# peripheral.net
KiCad netlist of a schematic drawn in Altium Designer
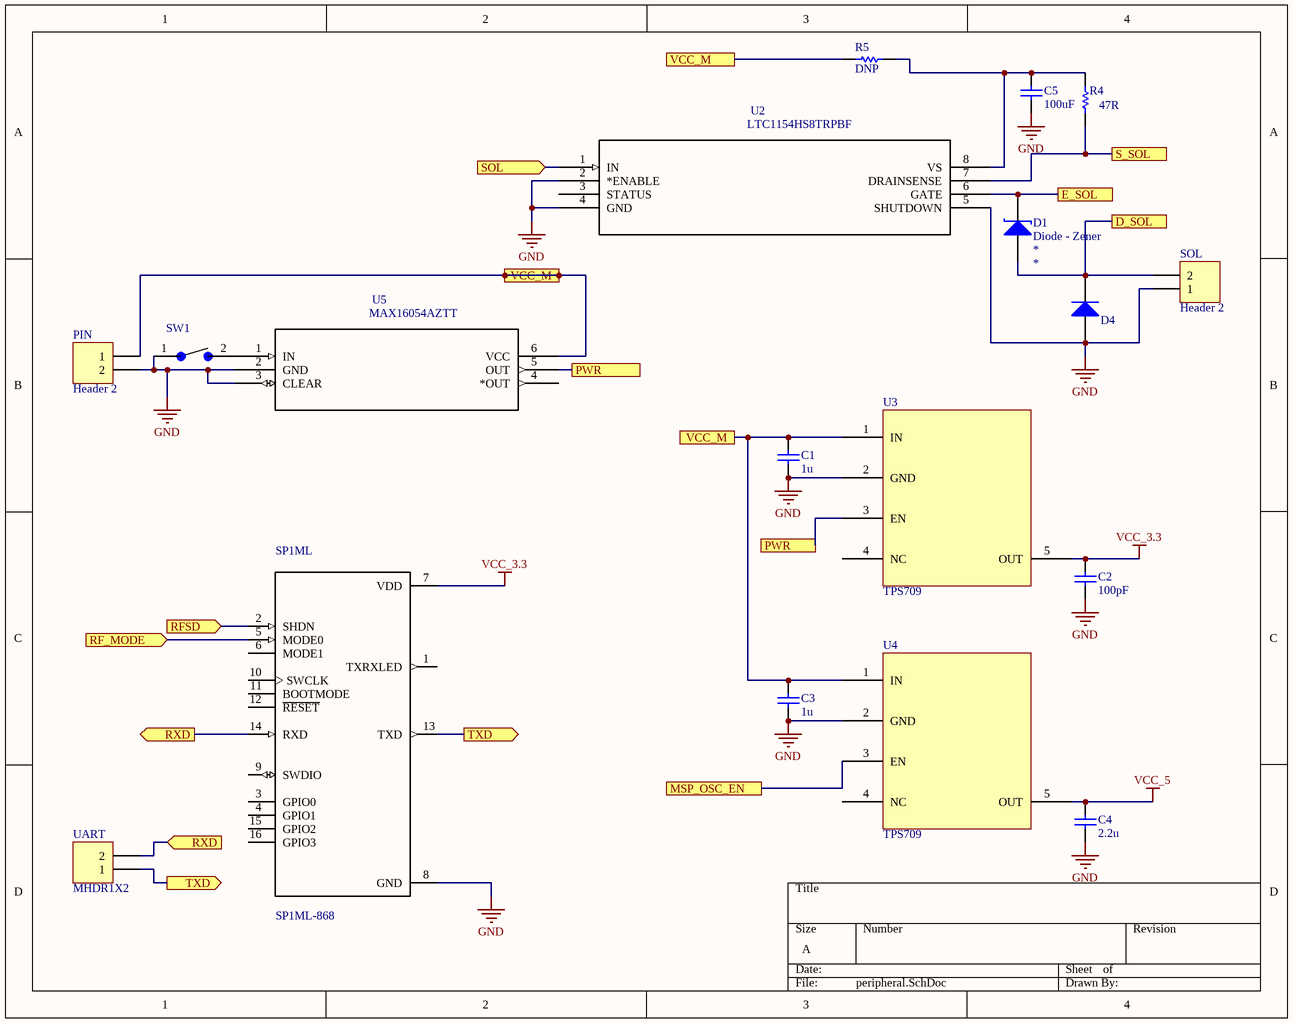
[diagram p0: peripheral.SchDoc]

(export (version "E")
  (design (tool "Eeschema 10.0.6"))
  (components
    (comp (ref "C1")
      (value "1u")
      (footprint "0402-W")
      (description "Ceramic Capacitor (Surface Mount)")
      (fields (field (name "MANUFACTURER") "Generic Ceramic Chip Cap (TBD)") (field (name "Comment") "Cap"))
      (libsource (lib "wisp") (part "Cap"))
    )
    (comp (ref "C2")
      (value "100pF")
      (footprint "0402-W")
      (description "Ceramic Capacitor (Surface Mount)")
      (fields (field (name "MANUFACTURER") "Generic Ceramic Chip Cap (TBD)") (field (name "Comment") "Cap"))
      (libsource (lib "wisp") (part "Cap"))
    )
    (comp (ref "C3")
      (value "1u")
      (footprint "0402-W")
      (description "Ceramic Capacitor (Surface Mount)")
      (fields (field (name "MANUFACTURER") "Generic Ceramic Chip Cap (TBD)") (field (name "Comment") "Cap"))
      (libsource (lib "wisp") (part "Cap"))
    )
    (comp (ref "C4")
      (value "2.2u")
      (footprint "0402-W")
      (description "Ceramic Capacitor (Surface Mount)")
      (fields (field (name "MANUFACTURER") "Generic Ceramic Chip Cap (TBD)") (field (name "Comment") "Cap"))
      (libsource (lib "wisp") (part "Cap"))
    )
    (comp (ref "C5")
      (value "100uF")
      (footprint "0402-W")
      (description "Ceramic Capacitor (Surface Mount)")
      (fields (field (name "MANUFACTURER") "Generic Ceramic Chip Cap (TBD)") (field (name "Comment") "Cap"))
      (libsource (lib "wisp") (part "Cap"))
    )
    (comp (ref "D1")
      (value "Diode - Zener")
      (footprint "SOD-523")
      (fields (field (name "ALTIUM_VALUE") "*") (field (name "RATING") "*"))
      (libsource (lib "wisp") (part "Diode - Zener"))
    )
    (comp (ref "D4")
      (value "Diode")
      (footprint "DIODE - SOD123")
      (description "General Purpose Diode")
      (libsource (lib "wisp") (part "Diode"))
    )
    (comp (ref "PIN")
      (value "Header 2")
      (footprint "HDR1X2")
      (description "Header, 2-Pin")
      (fields (field (name "PUBLISHER") "Altium Limited"))
      (libsource (lib "") (part "Header 2_1"))
    )
    (comp (ref "R4")
      (value "47R")
      (footprint "0402")
      (description "Chip Resistor (Surface Mount)")
      (fields (field (name "MANUFACTURER") "Generic Chip Res (TBD)") (field (name "Comment") "R_Pullup_1"))
      (libsource (lib "WISP_AD10") (part "Res"))
    )
    (comp (ref "R5")
      (value "DNP")
      (footprint "0402")
      (description "Chip Resistor (Surface Mount)")
      (fields (field (name "MANUFACTURER") "Generic Chip Res (TBD)") (field (name "Comment") "R_Pullup_1"))
      (libsource (lib "WISP_AD10") (part "Res"))
    )
    (comp (ref "SOL")
      (value "Header 2")
      (footprint "HDR1X2")
      (description "Header, 2-Pin")
      (fields (field (name "PUBLISHER") "Altium Limited"))
      (libsource (lib "Miscellaneous Connectors") (part "Header 2"))
    )
    (comp (ref "SP1ML")
      (value "SP1ML-868")
      (footprint "STM_SP1ML-868")
      (description "RF TXRX MODULE ISM<1GHZ CHIP ANT")
      (fields (field (name "MF") "STMicroelectronics"))
      (libsource (lib "SP1ML-868") (part "SP1ML-868"))
    )
    (comp (ref "SW1")
      (value "FSMSM _1437566-3_")
      (footprint "TE_FSMSM")
      (description "FSMSM=3.5X6 SMT TACT")
      (fields (field (name "MF") "TE Connectivity") (field (name "MP") "FSMSM"))
      (libsource (lib "FSMSM") (part "FSMSM"))
    )
    (comp (ref "U2")
      (value "LTC1154HS8TRPBF")
      (footprint "SOIC-8_S")
      (description "IC MOSFET DRIVER HIGH-SIDE 8SOIC")
      (fields (field (name "MF") "Linear Technology") (field (name "MP") "LTC1154HS8#TRPBF"))
      (libsource (lib "LTC1154HS8TRPBF") (part "LTC1154HS8TRPBF"))
    )
    (comp (ref "U3")
      (value "TPS709")
      (footprint "SOT95P280X145-5N")
      (description "Ultra low power Voltage Regulator")
      (libsource (lib "Fromm") (part "TPS709"))
    )
    (comp (ref "U4")
      (value "TPS709")
      (footprint "SOT95P280X145-5N")
      (description "Ultra low power Voltage Regulator")
      (libsource (lib "Fromm") (part "TPS709"))
    )
    (comp (ref "U5")
      (value "MAX16054AZTT")
      (footprint "21-0114C")
      (description "On/Off Controller With Debounce And +/-1")
      (fields (field (name "MF") "Maxim Integrated") (field (name "MP") "MAX16054AZT+"))
      (libsource (lib "MAX16054AZTT") (part "MAX16054AZTT"))
    )
    (comp (ref "UART")
      (value "MHDR1X2")
      (footprint "MHDR1X2")
      (description "Header, 2-Pin")
      (fields (field (name "PUBLISHER") "Altium Limited"))
      (libsource (lib "Miscellaneous Connectors") (part "MHDR1X2"))
    )
  )
  (nets
    (net (code "1") (name "/D_SOL") (class "Default")
      (node (ref "D1") (pin "1") (pinfunction "A_1") (pintype "passive"))
      (node (ref "D4") (pin "2") (pinfunction "C_2") (pintype "passive"))
      (node (ref "SOL") (pin "2") (pinfunction "2_2") (pintype "passive"))
    )
    (net (code "2") (name "/E_SOL") (class "Default")
      (node (ref "D1") (pin "2") (pinfunction "K_2") (pintype "passive"))
      (node (ref "U2") (pin "6") (pinfunction "GATE_6") (pintype "passive"))
    )
    (net (code "3") (name "/MSP_OSC_EN") (class "Default")
      (node (ref "U4") (pin "3") (pinfunction "EN_3") (pintype "passive"))
    )
    (net (code "4") (name "/PWR") (class "Default")
      (node (ref "U3") (pin "3") (pinfunction "EN_3") (pintype "passive"))
      (node (ref "U5") (pin "5") (pinfunction "OUT_5") (pintype "output"))
    )
    (net (code "5") (name "/RFSD") (class "Default")
      (node (ref "SP1ML") (pin "2") (pinfunction "SHDN_2") (pintype "input"))
    )
    (net (code "6") (name "/RF_MODE") (class "Default")
      (node (ref "SP1ML") (pin "5") (pinfunction "MODE0_5") (pintype "input"))
    )
    (net (code "7") (name "/RXD") (class "Default")
      (node (ref "SP1ML") (pin "14") (pinfunction "RXD_14") (pintype "input"))
      (node (ref "UART") (pin "2") (pinfunction "2_2") (pintype "passive"))
    )
    (net (code "8") (name "/SOL") (class "Default")
      (node (ref "U2") (pin "1") (pinfunction "IN_1") (pintype "input"))
    )
    (net (code "9") (name "/S_SOL") (class "Default")
      (node (ref "R4") (pin "1") (pinfunction "1_1") (pintype "passive"))
      (node (ref "U2") (pin "7") (pinfunction "DRAINSENSE_7") (pintype "passive"))
    )
    (net (code "10") (name "/TXD") (class "Default")
      (node (ref "SP1ML") (pin "13") (pinfunction "TXD_13") (pintype "output"))
      (node (ref "UART") (pin "1") (pinfunction "1_1") (pintype "passive"))
    )
    (net (code "11") (name "/VCC_M") (class "Default")
      (node (ref "C1") (pin "2") (pinfunction "2_2") (pintype "passive"))
      (node (ref "C3") (pin "2") (pinfunction "2_2") (pintype "passive"))
      (node (ref "PIN") (pin "1") (pinfunction "1_1") (pintype "passive"))
      (node (ref "R5") (pin "2") (pinfunction "2_2") (pintype "passive"))
      (node (ref "U3") (pin "1") (pinfunction "IN_1") (pintype "passive"))
      (node (ref "U4") (pin "1") (pinfunction "IN_1") (pintype "passive"))
      (node (ref "U5") (pin "6") (pinfunction "VCC_6") (pintype "power_in"))
    )
    (net (code "12") (name "GND") (class "Default")
      (node (ref "C1") (pin "1") (pinfunction "1_1") (pintype "passive"))
      (node (ref "C2") (pin "1") (pinfunction "1_1") (pintype "passive"))
      (node (ref "C3") (pin "1") (pinfunction "1_1") (pintype "passive"))
      (node (ref "C4") (pin "1") (pinfunction "1_1") (pintype "passive"))
      (node (ref "C5") (pin "1") (pinfunction "1_1") (pintype "passive"))
      (node (ref "D4") (pin "1") (pinfunction "A_1") (pintype "passive"))
      (node (ref "PIN") (pin "2") (pinfunction "2_2") (pintype "passive"))
      (node (ref "SOL") (pin "1") (pinfunction "1_1") (pintype "passive"))
      (node (ref "SP1ML") (pin "8") (pinfunction "GND_8") (pintype "passive"))
      (node (ref "SW1") (pin "1") (pinfunction "1_1") (pintype "passive"))
      (node (ref "U2") (pin "2") (pinfunction "*ENABLE_2") (pintype "passive"))
      (node (ref "U2") (pin "4") (pinfunction "GND_4") (pintype "power_in"))
      (node (ref "U2") (pin "5") (pinfunction "SHUTDOWN_5") (pintype "passive"))
      (node (ref "U3") (pin "2") (pinfunction "GND_2") (pintype "passive"))
      (node (ref "U4") (pin "2") (pinfunction "GND_2") (pintype "passive"))
      (node (ref "U5") (pin "2") (pinfunction "GND_2") (pintype "power_in"))
      (node (ref "U5") (pin "3") (pinfunction "CLEAR_3") (pintype "bidirectional"))
    )
    (net (code "13") (name "Net-(U2-VS)") (class "Default")
      (node (ref "C5") (pin "2") (pinfunction "2_2") (pintype "passive"))
      (node (ref "R4") (pin "2") (pinfunction "2_2") (pintype "passive"))
      (node (ref "R5") (pin "1") (pinfunction "1_1") (pintype "passive"))
      (node (ref "U2") (pin "8") (pinfunction "VS_8") (pintype "power_in"))
    )
    (net (code "14") (name "Net-(U5-IN)") (class "Default")
      (node (ref "SW1") (pin "2") (pinfunction "2_2") (pintype "passive"))
      (node (ref "U5") (pin "1") (pinfunction "IN_1") (pintype "input"))
    )
    (net (code "15") (name "VCC_3.3") (class "Default")
      (node (ref "C2") (pin "2") (pinfunction "2_2") (pintype "passive"))
      (node (ref "SP1ML") (pin "7") (pinfunction "VDD_7") (pintype "power_in"))
      (node (ref "U3") (pin "5") (pinfunction "OUT_5") (pintype "passive"))
    )
    (net (code "16") (name "VCC_5") (class "Default")
      (node (ref "C4") (pin "2") (pinfunction "2_2") (pintype "passive"))
      (node (ref "U4") (pin "5") (pinfunction "OUT_5") (pintype "passive"))
    )
    (net (code "17") (name "unconnected-(SP1ML-BOOTMODE-Pad11)") (class "Default")
      (node (ref "SP1ML") (pin "11") (pinfunction "BOOTMODE_11") (pintype "passive"))
    )
    (net (code "18") (name "unconnected-(SP1ML-GPIO0-Pad3)") (class "Default")
      (node (ref "SP1ML") (pin "3") (pinfunction "GPIO0_3") (pintype "passive"))
    )
    (net (code "19") (name "unconnected-(SP1ML-GPIO1-Pad4)") (class "Default")
      (node (ref "SP1ML") (pin "4") (pinfunction "GPIO1_4") (pintype "passive"))
    )
    (net (code "20") (name "unconnected-(SP1ML-GPIO2-Pad15)") (class "Default")
      (node (ref "SP1ML") (pin "15") (pinfunction "GPIO2_15") (pintype "passive"))
    )
    (net (code "21") (name "unconnected-(SP1ML-GPIO3-Pad16)") (class "Default")
      (node (ref "SP1ML") (pin "16") (pinfunction "GPIO3_16") (pintype "passive"))
    )
    (net (code "22") (name "unconnected-(SP1ML-MODE1-Pad6)") (class "Default")
      (node (ref "SP1ML") (pin "6") (pinfunction "MODE1_6") (pintype "passive"))
    )
    (net (code "23") (name "unconnected-(SP1ML-SWCLK-Pad10)") (class "Default")
      (node (ref "SP1ML") (pin "10") (pinfunction "SWCLK_10") (pintype "passive"))
    )
    (net (code "24") (name "unconnected-(SP1ML-SWDIO-Pad9)") (class "Default")
      (node (ref "SP1ML") (pin "9") (pinfunction "SWDIO_9") (pintype "bidirectional"))
    )
    (net (code "25") (name "unconnected-(SP1ML-TXRXLED-Pad1)") (class "Default")
      (node (ref "SP1ML") (pin "1") (pinfunction "TXRXLED_1") (pintype "output"))
    )
    (net (code "26") (name "unconnected-(SP1ML-~{RESET}-Pad12)") (class "Default")
      (node (ref "SP1ML") (pin "12") (pinfunction "~{RESET}_12") (pintype "passive"))
    )
    (net (code "27") (name "unconnected-(U2-STATUS-Pad3)") (class "Default")
      (node (ref "U2") (pin "3") (pinfunction "STATUS_3") (pintype "passive"))
    )
    (net (code "28") (name "unconnected-(U3-NC-Pad4)") (class "Default")
      (node (ref "U3") (pin "4") (pinfunction "NC_4") (pintype "passive"))
    )
    (net (code "29") (name "unconnected-(U4-NC-Pad4)") (class "Default")
      (node (ref "U4") (pin "4") (pinfunction "NC_4") (pintype "passive"))
    )
    (net (code "30") (name "unconnected-(U5-*OUT-Pad4)") (class "Default")
      (node (ref "U5") (pin "4") (pinfunction "*OUT_4") (pintype "output"))
    )
  )
)
